# Joint_Controller_Circuit.net
KiCad netlist of a schematic drawn in EAGLE
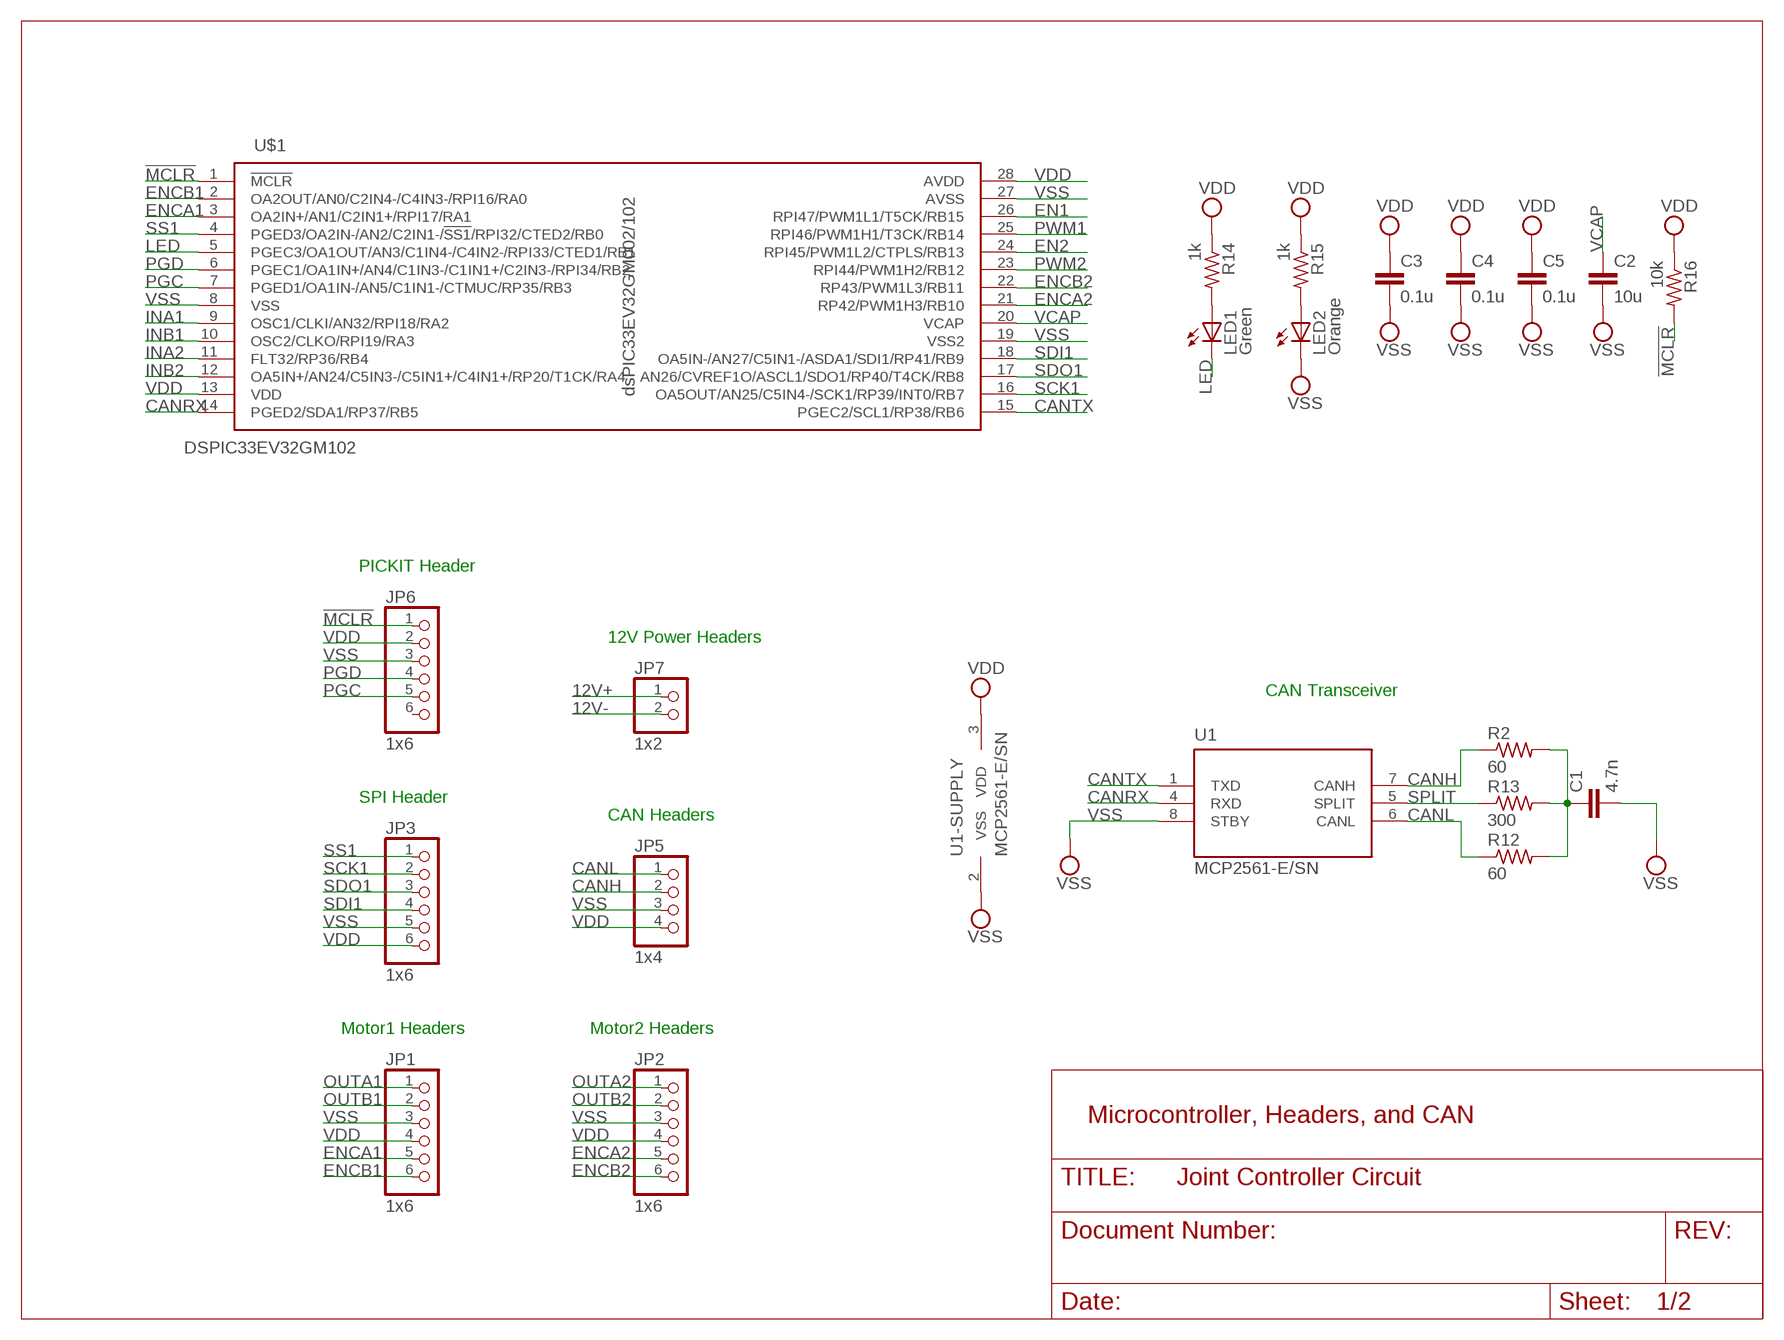
[diagram p0: schematic, sheet 1]
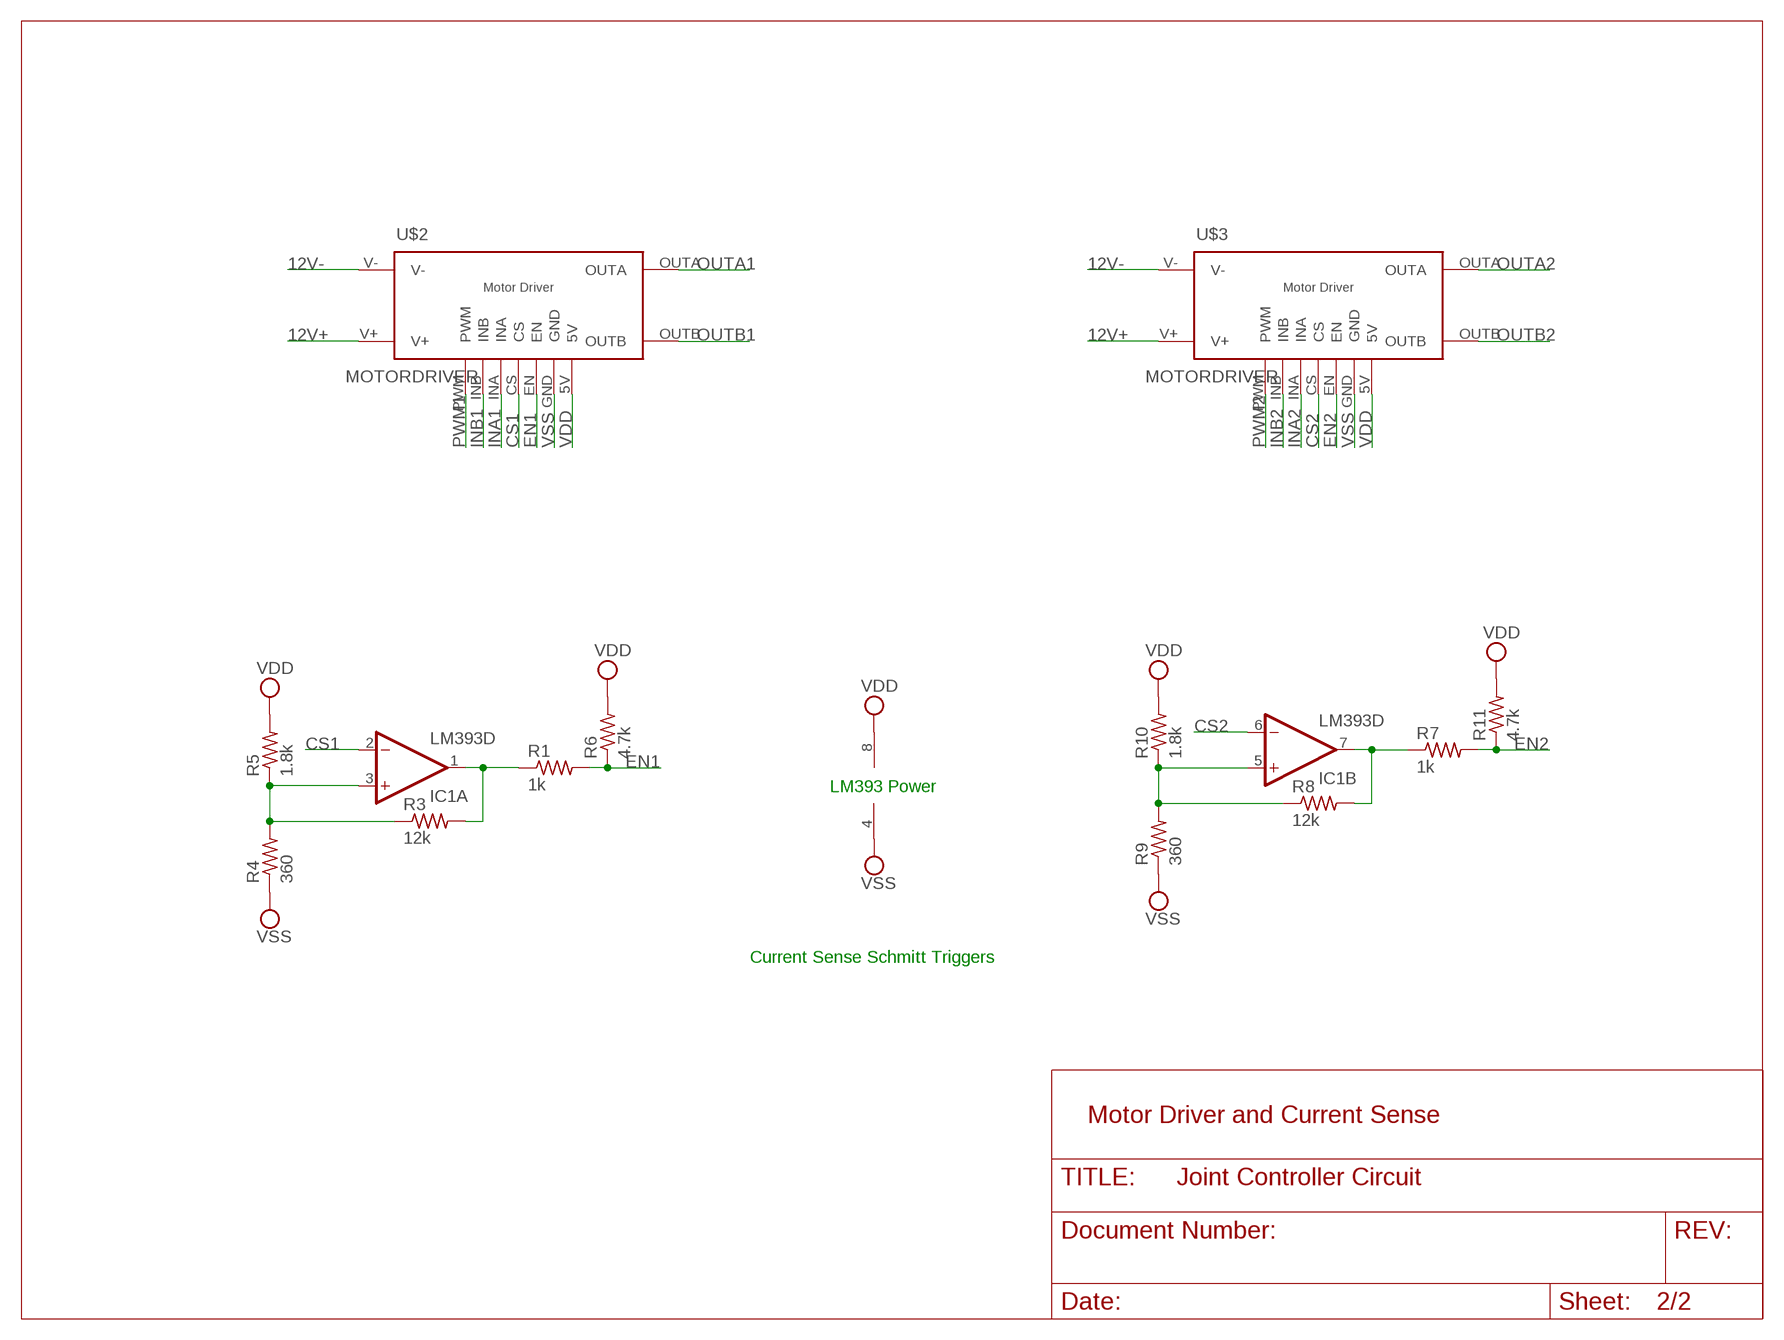
[diagram p1: schematic, sheet 2]

(export (version "E")
  (design (tool "Eeschema 10.0.6"))
  (components
    (comp (ref "C1")
      (value "4.7n")
      (footprint "eagle-import:C0805")
      (libsource (lib "eagle-import") (part "C-EUC0805"))
    )
    (comp (ref "C2")
      (value "10u")
      (footprint "eagle-import:C0805")
      (libsource (lib "eagle-import") (part "C-EUC0805"))
    )
    (comp (ref "C3")
      (value "0.1u")
      (footprint "eagle-import:C0805")
      (libsource (lib "eagle-import") (part "C-EUC0805"))
    )
    (comp (ref "C4")
      (value "0.1u")
      (footprint "eagle-import:C0805")
      (libsource (lib "eagle-import") (part "C-EUC0805"))
    )
    (comp (ref "C5")
      (value "0.1u")
      (footprint "eagle-import:C0805")
      (libsource (lib "eagle-import") (part "C-EUC0805"))
    )
    (comp (ref "JP1")
      (value "1x6")
      (footprint "eagle-import:1X06")
      (libsource (lib "eagle-import") (part "PINHD-1X6"))
    )
    (comp (ref "JP2")
      (value "1x6")
      (footprint "eagle-import:1X06")
      (libsource (lib "eagle-import") (part "PINHD-1X6"))
    )
    (comp (ref "JP3")
      (value "1x6")
      (footprint "eagle-import:1X06")
      (libsource (lib "eagle-import") (part "PINHD-1X6"))
    )
    (comp (ref "JP5")
      (value "1x4")
      (footprint "eagle-import:1X04")
      (libsource (lib "eagle-import") (part "PINHD-1X4"))
    )
    (comp (ref "JP6")
      (value "1x6")
      (footprint "eagle-import:1X06")
      (libsource (lib "eagle-import") (part "PINHD-1X6"))
    )
    (comp (ref "JP7")
      (value "1x2")
      (footprint "eagle-import:1X02")
      (libsource (lib "eagle-import") (part "PINHD-1X2"))
    )
    (comp (ref "LED1")
      (value "Green")
      (footprint "eagle-import:CHIP-LED0805")
      (libsource (lib "eagle-import") (part "LEDCHIP-LED0805"))
    )
    (comp (ref "LED2")
      (value "Orange")
      (footprint "eagle-import:CHIP-LED0805")
      (libsource (lib "eagle-import") (part "LEDCHIP-LED0805"))
    )
    (comp (ref "R2")
      (value "60")
      (footprint "eagle-import:R0805")
      (libsource (lib "eagle-import") (part "R-US_R0805"))
    )
    (comp (ref "R12")
      (value "60")
      (footprint "eagle-import:R0805")
      (libsource (lib "eagle-import") (part "R-US_R0805"))
    )
    (comp (ref "R13")
      (value "300")
      (footprint "eagle-import:R0805")
      (libsource (lib "eagle-import") (part "R-US_R0805"))
    )
    (comp (ref "R14")
      (value "1k")
      (footprint "eagle-import:R0805")
      (libsource (lib "eagle-import") (part "R-US_R0805"))
    )
    (comp (ref "R15")
      (value "1k")
      (footprint "eagle-import:R0805")
      (libsource (lib "eagle-import") (part "R-US_R0805"))
    )
    (comp (ref "R16")
      (value "10k")
      (footprint "eagle-import:R0805")
      (libsource (lib "eagle-import") (part "R-US_R0805"))
    )
    (comp (ref "U$1")
      (value "DSPIC33EV32GM102")
      (footprint "eagle-import:SOIC28")
      (libsource (lib "eagle-import") (part "DSPIC33EV32GM102"))
    )
    (comp (ref "U1")
      (value "MCP2561-E/SN")
      (footprint "eagle-import:SOIC-8")
      (fields (field (name "MANUFACTURER") "Microchip Technology"))
      (libsource (lib "eagle-import") (part "MCP2561-/?SNE"))
    )
    (comp (ref "IC1")
      (value "LM393D")
      (footprint "eagle-import:SO08")
      (libsource (lib "eagle-import") (part "LM393D"))
    )
    (comp (ref "R1")
      (value "1k")
      (footprint "eagle-import:R0805")
      (libsource (lib "eagle-import") (part "R-US_R0805"))
    )
    (comp (ref "R3")
      (value "12k")
      (footprint "eagle-import:R0805")
      (libsource (lib "eagle-import") (part "R-US_R0805"))
    )
    (comp (ref "R4")
      (value "360")
      (footprint "eagle-import:R0805")
      (libsource (lib "eagle-import") (part "R-US_R0805"))
    )
    (comp (ref "R5")
      (value "1.8k")
      (footprint "eagle-import:R0805")
      (libsource (lib "eagle-import") (part "R-US_R0805"))
    )
    (comp (ref "R6")
      (value "4.7k")
      (footprint "eagle-import:R0805")
      (libsource (lib "eagle-import") (part "R-US_R0805"))
    )
    (comp (ref "R7")
      (value "1k")
      (footprint "eagle-import:R0805")
      (libsource (lib "eagle-import") (part "R-US_R0805"))
    )
    (comp (ref "R8")
      (value "12k")
      (footprint "eagle-import:R0805")
      (libsource (lib "eagle-import") (part "R-US_R0805"))
    )
    (comp (ref "R9")
      (value "360")
      (footprint "eagle-import:R0805")
      (libsource (lib "eagle-import") (part "R-US_R0805"))
    )
    (comp (ref "R10")
      (value "1.8k")
      (footprint "eagle-import:R0805")
      (libsource (lib "eagle-import") (part "R-US_R0805"))
    )
    (comp (ref "R11")
      (value "4.7k")
      (footprint "eagle-import:R0805")
      (libsource (lib "eagle-import") (part "R-US_R0805"))
    )
    (comp (ref "U$2")
      (value "MOTORDRIVER")
      (footprint "eagle-import:MOTORDRIVER")
      (libsource (lib "eagle-import") (part "MOTORDRIVER"))
    )
    (comp (ref "U$3")
      (value "MOTORDRIVER")
      (footprint "eagle-import:MOTORDRIVER")
      (libsource (lib "eagle-import") (part "MOTORDRIVER"))
    )
  )
  (nets
    (net (code "1") (name "12V+") (class "Default")
      (node (ref "JP7") (pin "1") (pinfunction "1_1") (pintype "passive"))
      (node (ref "U$2") (pin "V+") (pinfunction "V+_V+") (pintype "bidirectional"))
      (node (ref "U$3") (pin "V+") (pinfunction "V+_V+") (pintype "bidirectional"))
    )
    (net (code "2") (name "12V-") (class "Default")
      (node (ref "JP7") (pin "2") (pinfunction "2_2") (pintype "passive"))
      (node (ref "U$2") (pin "V-") (pinfunction "V-_V-") (pintype "bidirectional"))
      (node (ref "U$3") (pin "V-") (pinfunction "V-_V-") (pintype "bidirectional"))
    )
    (net (code "3") (name "CANH") (class "Default")
      (node (ref "JP5") (pin "2") (pinfunction "2_2") (pintype "passive"))
      (node (ref "R2") (pin "1") (pinfunction "1_1") (pintype "passive"))
      (node (ref "U1") (pin "7") (pinfunction "CANH_7") (pintype "bidirectional"))
    )
    (net (code "4") (name "CANL") (class "Default")
      (node (ref "JP5") (pin "1") (pinfunction "1_1") (pintype "passive"))
      (node (ref "R12") (pin "1") (pinfunction "1_1") (pintype "passive"))
      (node (ref "U1") (pin "6") (pinfunction "CANL_6") (pintype "bidirectional"))
    )
    (net (code "5") (name "CANRX") (class "Default")
      (node (ref "U$1") (pin "14") (pinfunction "PGED2/SDA1/RP37/RB5_14") (pintype "bidirectional"))
      (node (ref "U1") (pin "4") (pinfunction "RXD_4") (pintype "bidirectional"))
    )
    (net (code "6") (name "CANTX") (class "Default")
      (node (ref "U$1") (pin "15") (pinfunction "PGEC2/SCL1/RP38/RB6_15") (pintype "bidirectional"))
      (node (ref "U1") (pin "1") (pinfunction "TXD_1") (pintype "bidirectional"))
    )
    (net (code "7") (name "CS1") (class "Default")
      (node (ref "IC1") (pin "2") (pinfunction "-IN_2") (pintype "input"))
      (node (ref "U$2") (pin "CS") (pinfunction "CS_CS") (pintype "bidirectional"))
    )
    (net (code "8") (name "CS2") (class "Default")
      (node (ref "IC1") (pin "6") (pinfunction "-IN_6") (pintype "input"))
      (node (ref "U$3") (pin "CS") (pinfunction "CS_CS") (pintype "bidirectional"))
    )
    (net (code "9") (name "EN1") (class "Default")
      (node (ref "R1") (pin "2") (pinfunction "2_2") (pintype "passive"))
      (node (ref "R6") (pin "1") (pinfunction "1_1") (pintype "passive"))
      (node (ref "U$1") (pin "26") (pinfunction "RPI47/PWM1L1/T5CK/RB15_26") (pintype "bidirectional"))
      (node (ref "U$2") (pin "EN") (pinfunction "EN_EN") (pintype "bidirectional"))
    )
    (net (code "10") (name "EN2") (class "Default")
      (node (ref "R11") (pin "1") (pinfunction "1_1") (pintype "passive"))
      (node (ref "R7") (pin "2") (pinfunction "2_2") (pintype "passive"))
      (node (ref "U$1") (pin "24") (pinfunction "RPI45/PWM1L2/CTPLS/RB13_24") (pintype "bidirectional"))
      (node (ref "U$3") (pin "EN") (pinfunction "EN_EN") (pintype "bidirectional"))
    )
    (net (code "11") (name "ENCA1") (class "Default")
      (node (ref "JP1") (pin "5") (pinfunction "5_5") (pintype "passive"))
      (node (ref "U$1") (pin "3") (pinfunction "OA2IN+/AN1/C2IN1+/RPI17/RA1_3") (pintype "bidirectional"))
    )
    (net (code "12") (name "ENCA2") (class "Default")
      (node (ref "JP2") (pin "5") (pinfunction "5_5") (pintype "passive"))
      (node (ref "U$1") (pin "21") (pinfunction "RP42/PWM1H3/RB10_21") (pintype "bidirectional"))
    )
    (net (code "13") (name "ENCB1") (class "Default")
      (node (ref "JP1") (pin "6") (pinfunction "6_6") (pintype "passive"))
      (node (ref "U$1") (pin "2") (pinfunction "OA2OUT/AN0/C2IN4-/C4IN3-/RPI16/RA0_2") (pintype "bidirectional"))
    )
    (net (code "14") (name "ENCB2") (class "Default")
      (node (ref "JP2") (pin "6") (pinfunction "6_6") (pintype "passive"))
      (node (ref "U$1") (pin "22") (pinfunction "RP43/PWM1L3/RB11_22") (pintype "bidirectional"))
    )
    (net (code "15") (name "INA1") (class "Default")
      (node (ref "U$1") (pin "9") (pinfunction "OSC1/CLKI/AN32/RPI18/RA2_9") (pintype "bidirectional"))
      (node (ref "U$2") (pin "INA") (pinfunction "INA_INA") (pintype "bidirectional"))
    )
    (net (code "16") (name "INA2") (class "Default")
      (node (ref "U$1") (pin "11") (pinfunction "FLT32/RP36/RB4_11") (pintype "bidirectional"))
      (node (ref "U$3") (pin "INA") (pinfunction "INA_INA") (pintype "bidirectional"))
    )
    (net (code "17") (name "INB1") (class "Default")
      (node (ref "U$1") (pin "10") (pinfunction "OSC2/CLKO/RPI19/RA3_10") (pintype "bidirectional"))
      (node (ref "U$2") (pin "INB") (pinfunction "INB_INB") (pintype "bidirectional"))
    )
    (net (code "18") (name "INB2") (class "Default")
      (node (ref "U$1") (pin "12") (pinfunction "OA5IN+/AN24/C5IN3-/C5IN1+/C4IN1+/RP20/T1CK/RA4_12") (pintype "bidirectional"))
      (node (ref "U$3") (pin "INB") (pinfunction "INB_INB") (pintype "bidirectional"))
    )
    (net (code "19") (name "LED") (class "Default")
      (node (ref "LED1") (pin "C") (pinfunction "C_C") (pintype "passive"))
      (node (ref "U$1") (pin "5") (pinfunction "PGEC3/OA1OUT/AN3/C1IN4-/C4IN2-/RPI33/CTED1/RB1_5") (pintype "bidirectional"))
    )
    (net (code "20") (name "Net-(C1-Pad1)") (class "Default")
      (node (ref "C1") (pin "1") (pinfunction "1_1") (pintype "passive"))
      (node (ref "R12") (pin "2") (pinfunction "2_2") (pintype "passive"))
      (node (ref "R13") (pin "2") (pinfunction "2_2") (pintype "passive"))
      (node (ref "R2") (pin "2") (pinfunction "2_2") (pintype "passive"))
    )
    (net (code "21") (name "Net-(IC1A-+IN)") (class "Default")
      (node (ref "IC1") (pin "3") (pinfunction "+IN_3") (pintype "input"))
      (node (ref "R3") (pin "1") (pinfunction "1_1") (pintype "passive"))
      (node (ref "R4") (pin "2") (pinfunction "2_2") (pintype "passive"))
      (node (ref "R5") (pin "1") (pinfunction "1_1") (pintype "passive"))
    )
    (net (code "22") (name "Net-(IC1A-OUT)") (class "Default")
      (node (ref "IC1") (pin "1") (pinfunction "OUT_1") (pintype "output"))
      (node (ref "R1") (pin "1") (pinfunction "1_1") (pintype "passive"))
      (node (ref "R3") (pin "2") (pinfunction "2_2") (pintype "passive"))
    )
    (net (code "23") (name "Net-(IC1B-+IN)") (class "Default")
      (node (ref "IC1") (pin "5") (pinfunction "+IN_5") (pintype "input"))
      (node (ref "R10") (pin "1") (pinfunction "1_1") (pintype "passive"))
      (node (ref "R8") (pin "1") (pinfunction "1_1") (pintype "passive"))
      (node (ref "R9") (pin "2") (pinfunction "2_2") (pintype "passive"))
    )
    (net (code "24") (name "Net-(IC1B-OUT)") (class "Default")
      (node (ref "IC1") (pin "7") (pinfunction "OUT_7") (pintype "output"))
      (node (ref "R7") (pin "1") (pinfunction "1_1") (pintype "passive"))
      (node (ref "R8") (pin "2") (pinfunction "2_2") (pintype "passive"))
    )
    (net (code "25") (name "Net-(LED1-PadA)") (class "Default")
      (node (ref "LED1") (pin "A") (pinfunction "A_A") (pintype "passive"))
      (node (ref "R14") (pin "2") (pinfunction "2_2") (pintype "passive"))
    )
    (net (code "26") (name "Net-(LED2-PadA)") (class "Default")
      (node (ref "LED2") (pin "A") (pinfunction "A_A") (pintype "passive"))
      (node (ref "R15") (pin "2") (pinfunction "2_2") (pintype "passive"))
    )
    (net (code "27") (name "OUTA1") (class "Default")
      (node (ref "JP1") (pin "1") (pinfunction "1_1") (pintype "passive"))
      (node (ref "U$2") (pin "OUTA") (pinfunction "OUTA_OUTA") (pintype "bidirectional"))
    )
    (net (code "28") (name "OUTA2") (class "Default")
      (node (ref "JP2") (pin "1") (pinfunction "1_1") (pintype "passive"))
      (node (ref "U$3") (pin "OUTA") (pinfunction "OUTA_OUTA") (pintype "bidirectional"))
    )
    (net (code "29") (name "OUTB1") (class "Default")
      (node (ref "JP1") (pin "2") (pinfunction "2_2") (pintype "passive"))
      (node (ref "U$2") (pin "OUTB") (pinfunction "OUTB_OUTB") (pintype "bidirectional"))
    )
    (net (code "30") (name "OUTB2") (class "Default")
      (node (ref "JP2") (pin "2") (pinfunction "2_2") (pintype "passive"))
      (node (ref "U$3") (pin "OUTB") (pinfunction "OUTB_OUTB") (pintype "bidirectional"))
    )
    (net (code "31") (name "PGC") (class "Default")
      (node (ref "JP6") (pin "5") (pinfunction "5_5") (pintype "passive"))
      (node (ref "U$1") (pin "7") (pinfunction "PGED1/OA1IN-/AN5/C1IN1-/CTMUC/RP35/RB3_7") (pintype "bidirectional"))
    )
    (net (code "32") (name "PGD") (class "Default")
      (node (ref "JP6") (pin "4") (pinfunction "4_4") (pintype "passive"))
      (node (ref "U$1") (pin "6") (pinfunction "PGEC1/OA1IN+/AN4/C1IN3-/C1IN1+/C2IN3-/RPI34/RB2_6") (pintype "bidirectional"))
    )
    (net (code "33") (name "PWM1") (class "Default")
      (node (ref "U$1") (pin "25") (pinfunction "RPI46/PWM1H1/T3CK/RB14_25") (pintype "bidirectional"))
      (node (ref "U$2") (pin "PWM") (pinfunction "PWM_PWM") (pintype "bidirectional"))
    )
    (net (code "34") (name "PWM2") (class "Default")
      (node (ref "U$1") (pin "23") (pinfunction "RPI44/PWM1H2/RB12_23") (pintype "bidirectional"))
      (node (ref "U$3") (pin "PWM") (pinfunction "PWM_PWM") (pintype "bidirectional"))
    )
    (net (code "35") (name "SCK1") (class "Default")
      (node (ref "JP3") (pin "2") (pinfunction "2_2") (pintype "passive"))
      (node (ref "U$1") (pin "16") (pinfunction "OA5OUT/AN25/C5IN4-/SCK1/RP39/INT0/RB7_16") (pintype "bidirectional"))
    )
    (net (code "36") (name "SDI1") (class "Default")
      (node (ref "JP3") (pin "4") (pinfunction "4_4") (pintype "passive"))
      (node (ref "U$1") (pin "18") (pinfunction "OA5IN-/AN27/C5IN1-/ASDA1/SDI1/RP41/RB9_18") (pintype "bidirectional"))
    )
    (net (code "37") (name "SDO1") (class "Default")
      (node (ref "JP3") (pin "3") (pinfunction "3_3") (pintype "passive"))
      (node (ref "U$1") (pin "17") (pinfunction "AN26/CVREF1O/ASCL1/SDO1/RP40/T4CK/RB8_17") (pintype "bidirectional"))
    )
    (net (code "38") (name "SPLIT") (class "Default")
      (node (ref "R13") (pin "1") (pinfunction "1_1") (pintype "passive"))
      (node (ref "U1") (pin "5") (pinfunction "SPLIT_5") (pintype "bidirectional"))
    )
    (net (code "39") (name "SS1") (class "Default")
      (node (ref "JP3") (pin "1") (pinfunction "1_1") (pintype "passive"))
      (node (ref "U$1") (pin "4") (pinfunction "PGED3/OA2IN-/AN2/C2IN1-/~{SS1}/RPI32/CTED2/RB0_4") (pintype "bidirectional"))
    )
    (net (code "40") (name "VCAP") (class "Default")
      (node (ref "C2") (pin "1") (pinfunction "1_1") (pintype "passive"))
      (node (ref "U$1") (pin "20") (pinfunction "VCAP_20") (pintype "bidirectional"))
    )
    (net (code "41") (name "VDD") (class "Default")
      (node (ref "C3") (pin "1") (pinfunction "1_1") (pintype "passive"))
      (node (ref "C4") (pin "1") (pinfunction "1_1") (pintype "passive"))
      (node (ref "C5") (pin "1") (pinfunction "1_1") (pintype "passive"))
      (node (ref "IC1") (pin "8") (pinfunction "V+_8") (pintype "power_in"))
      (node (ref "JP1") (pin "4") (pinfunction "4_4") (pintype "passive"))
      (node (ref "JP2") (pin "4") (pinfunction "4_4") (pintype "passive"))
      (node (ref "JP3") (pin "6") (pinfunction "6_6") (pintype "passive"))
      (node (ref "JP5") (pin "4") (pinfunction "4_4") (pintype "passive"))
      (node (ref "JP6") (pin "2") (pinfunction "2_2") (pintype "passive"))
      (node (ref "R10") (pin "2") (pinfunction "2_2") (pintype "passive"))
      (node (ref "R11") (pin "2") (pinfunction "2_2") (pintype "passive"))
      (node (ref "R14") (pin "1") (pinfunction "1_1") (pintype "passive"))
      (node (ref "R15") (pin "1") (pinfunction "1_1") (pintype "passive"))
      (node (ref "R16") (pin "1") (pinfunction "1_1") (pintype "passive"))
      (node (ref "R5") (pin "2") (pinfunction "2_2") (pintype "passive"))
      (node (ref "R6") (pin "2") (pinfunction "2_2") (pintype "passive"))
      (node (ref "U$1") (pin "13") (pinfunction "VDD_13") (pintype "bidirectional"))
      (node (ref "U$1") (pin "28") (pinfunction "AVDD_28") (pintype "bidirectional"))
      (node (ref "U$2") (pin "5V") (pinfunction "5V_5V") (pintype "bidirectional"))
      (node (ref "U$3") (pin "5V") (pinfunction "5V_5V") (pintype "bidirectional"))
      (node (ref "U1") (pin "3") (pinfunction "VDD_3") (pintype "power_in"))
    )
    (net (code "42") (name "VSS") (class "Default")
      (node (ref "C1") (pin "2") (pinfunction "2_2") (pintype "passive"))
      (node (ref "C2") (pin "2") (pinfunction "2_2") (pintype "passive"))
      (node (ref "C3") (pin "2") (pinfunction "2_2") (pintype "passive"))
      (node (ref "C4") (pin "2") (pinfunction "2_2") (pintype "passive"))
      (node (ref "C5") (pin "2") (pinfunction "2_2") (pintype "passive"))
      (node (ref "IC1") (pin "4") (pinfunction "V-_4") (pintype "power_in"))
      (node (ref "JP1") (pin "3") (pinfunction "3_3") (pintype "passive"))
      (node (ref "JP2") (pin "3") (pinfunction "3_3") (pintype "passive"))
      (node (ref "JP3") (pin "5") (pinfunction "5_5") (pintype "passive"))
      (node (ref "JP5") (pin "3") (pinfunction "3_3") (pintype "passive"))
      (node (ref "JP6") (pin "3") (pinfunction "3_3") (pintype "passive"))
      (node (ref "LED2") (pin "C") (pinfunction "C_C") (pintype "passive"))
      (node (ref "R4") (pin "1") (pinfunction "1_1") (pintype "passive"))
      (node (ref "R9") (pin "1") (pinfunction "1_1") (pintype "passive"))
      (node (ref "U$1") (pin "19") (pinfunction "VSS2_19") (pintype "bidirectional"))
      (node (ref "U$1") (pin "27") (pinfunction "AVSS_27") (pintype "bidirectional"))
      (node (ref "U$1") (pin "8") (pinfunction "VSS_8") (pintype "bidirectional"))
      (node (ref "U$2") (pin "GND") (pinfunction "GND_GND") (pintype "bidirectional"))
      (node (ref "U$3") (pin "GND") (pinfunction "GND_GND") (pintype "bidirectional"))
      (node (ref "U1") (pin "2") (pinfunction "VSS_2") (pintype "power_in"))
      (node (ref "U1") (pin "8") (pinfunction "STBY_8") (pintype "bidirectional"))
    )
    (net (code "43") (name "unconnected-(JP6-Pad6)") (class "Default")
      (node (ref "JP6") (pin "6") (pinfunction "6_6") (pintype "passive"))
    )
    (net (code "44") (name "~{MCLR}") (class "Default")
      (node (ref "JP6") (pin "1") (pinfunction "1_1") (pintype "passive"))
      (node (ref "R16") (pin "2") (pinfunction "2_2") (pintype "passive"))
      (node (ref "U$1") (pin "1") (pinfunction "~{MCLR}_1") (pintype "bidirectional"))
    )
  )
)
